# POWR0009.net
KiCad netlist of a schematic drawn in Altium Designer
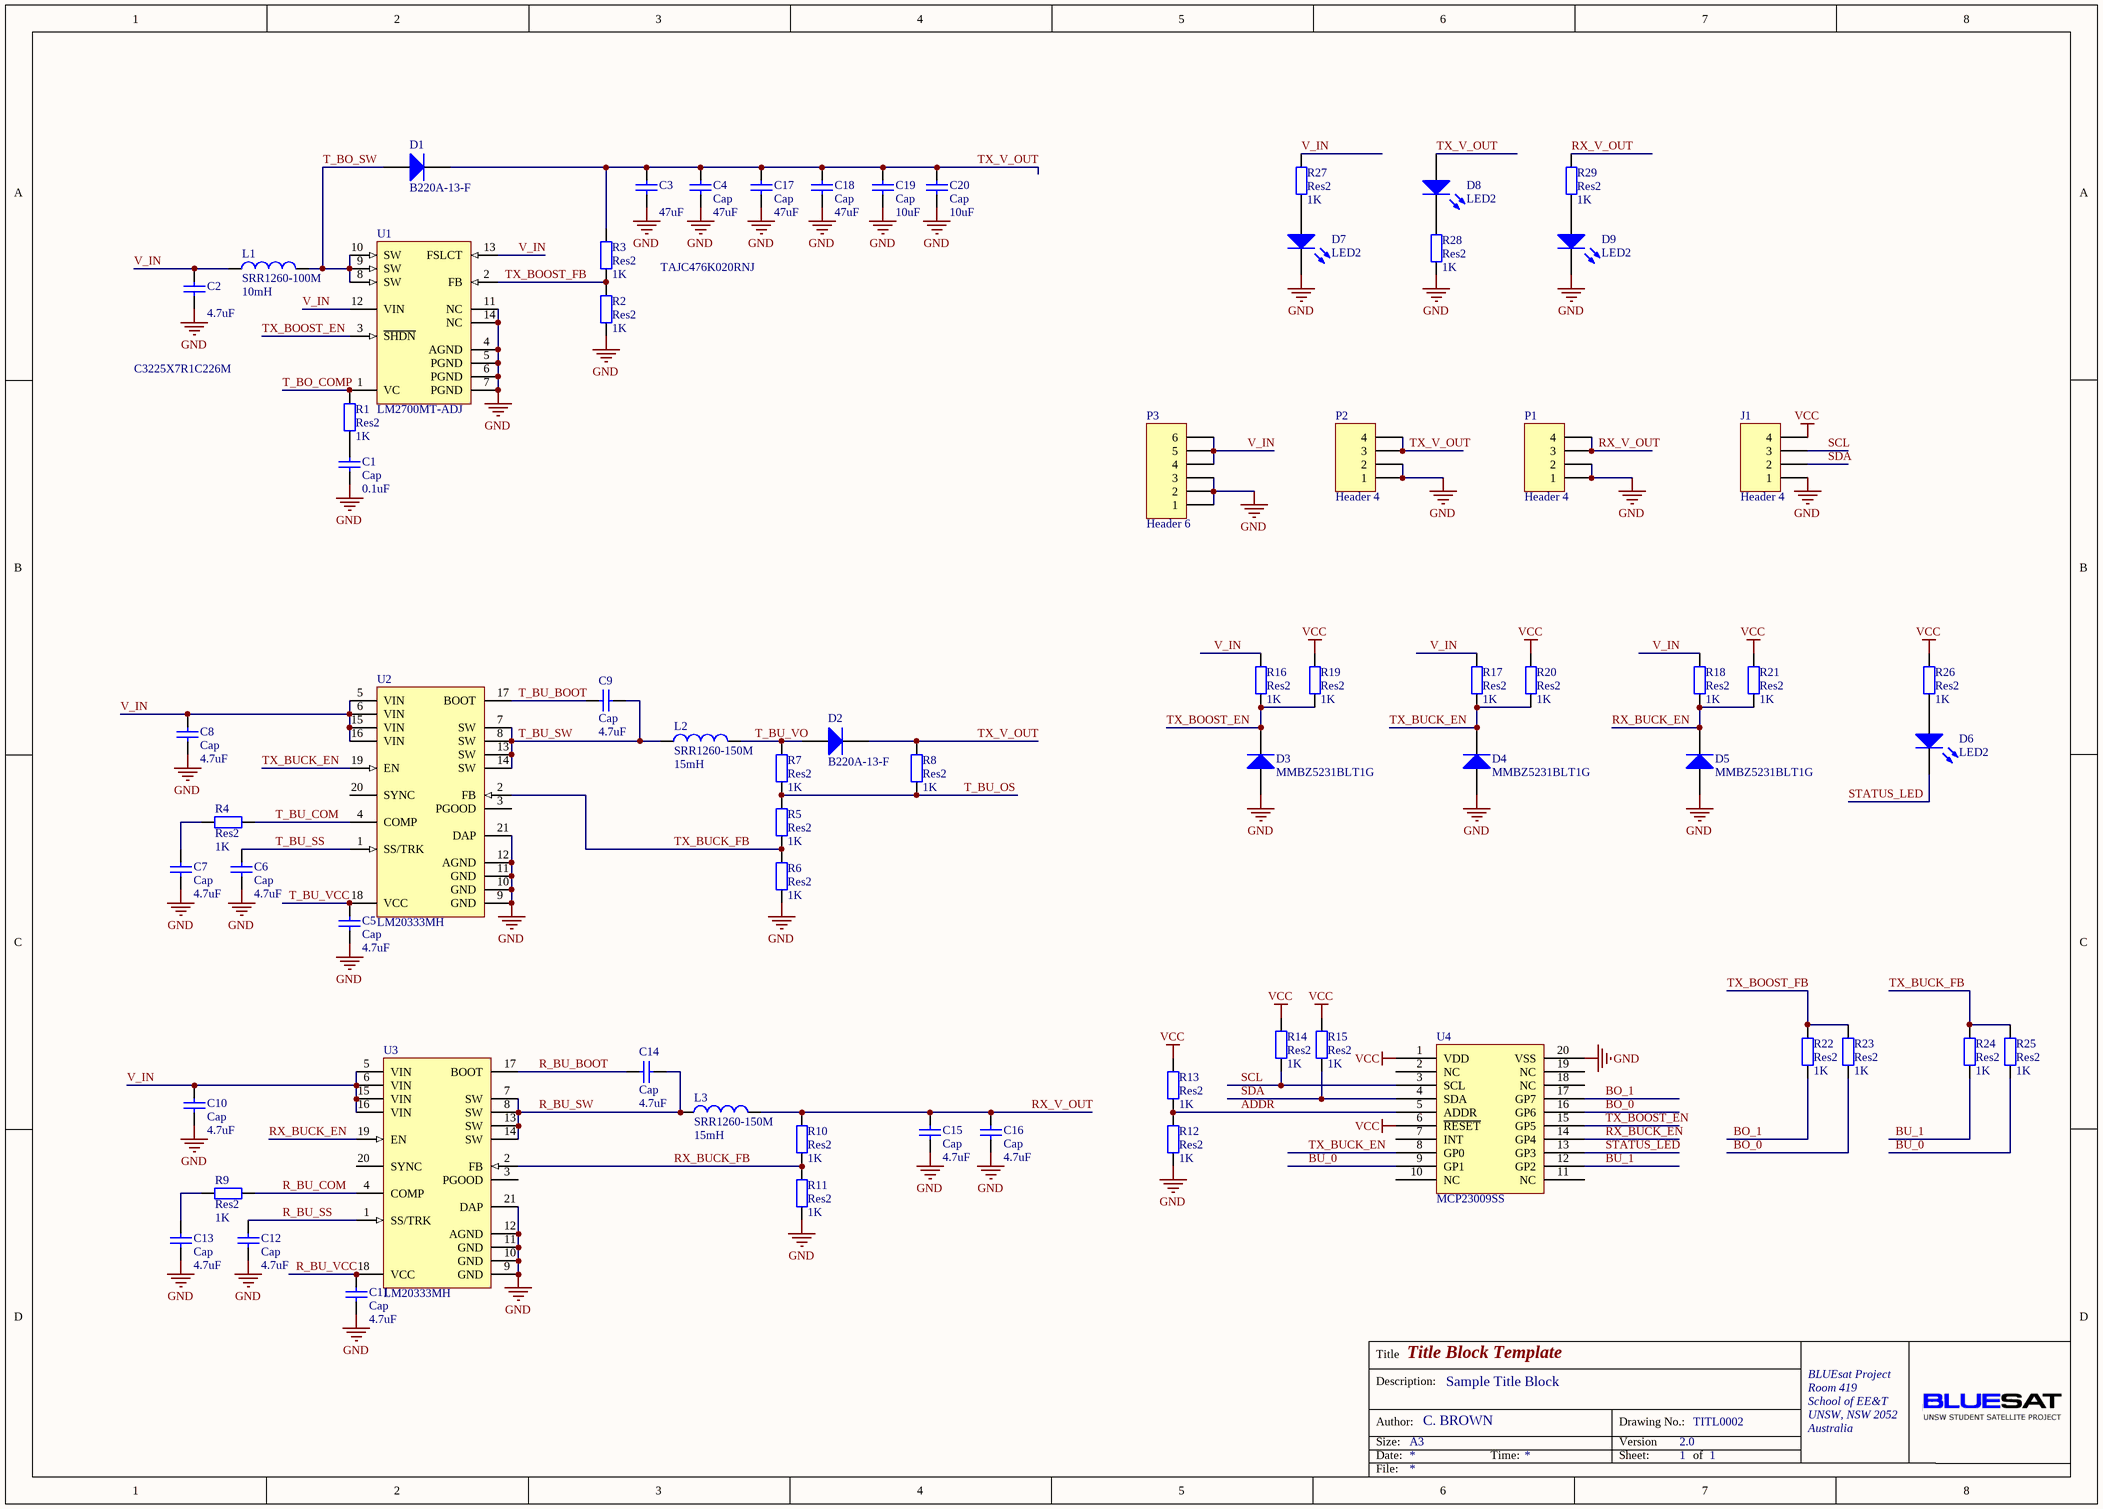
[diagram p0: POWR0009.SchDoc]

(export (version "E")
  (design (tool "Eeschema 10.0.6"))
  (components
    (comp (ref "C1")
      (value "Cap")
      (footprint "R0805M")
      (description "Capacitor")
      (fields (field (name "ALTIUM_VALUE") "0.1uF") (field (name "PUBLISHER") "Altium Limited"))
      (libsource (lib "Miscellaneous Devices") (part "Cap"))
    )
    (comp (ref "C2")
      (value "C3225X7R1C226M")
      (footprint "R1210M")
      (description "Capacitor")
      (fields (field (name "ALTIUM_VALUE") "4.7uF") (field (name "PUBLISHER") "Altium Limited"))
      (libsource (lib "Miscellaneous Devices") (part "Cap"))
    )
    (comp (ref "C3")
      (value "TAJC476K020RNJ")
      (footprint "TANTCASEC")
      (description "Capacitor")
      (fields (field (name "ALTIUM_VALUE") "47uF") (field (name "PUBLISHER") "Altium Limited"))
      (libsource (lib "Miscellaneous Devices") (part "Cap"))
    )
    (comp (ref "C4")
      (value "Cap")
      (footprint "TANTCASEC")
      (description "Capacitor")
      (fields (field (name "ALTIUM_VALUE") "47uF") (field (name "PUBLISHER") "Altium Limited"))
      (libsource (lib "Miscellaneous Devices") (part "Cap"))
    )
    (comp (ref "C5")
      (value "Cap")
      (footprint "R0805M")
      (description "Capacitor")
      (fields (field (name "ALTIUM_VALUE") "4.7uF") (field (name "PUBLISHER") "Altium Limited"))
      (libsource (lib "Miscellaneous Devices") (part "Cap"))
    )
    (comp (ref "C6")
      (value "Cap")
      (footprint "R0805M")
      (description "Capacitor")
      (fields (field (name "ALTIUM_VALUE") "4.7uF") (field (name "PUBLISHER") "Altium Limited"))
      (libsource (lib "Miscellaneous Devices") (part "Cap"))
    )
    (comp (ref "C7")
      (value "Cap")
      (footprint "R0805M")
      (description "Capacitor")
      (fields (field (name "ALTIUM_VALUE") "4.7uF") (field (name "PUBLISHER") "Altium Limited"))
      (libsource (lib "Miscellaneous Devices") (part "Cap"))
    )
    (comp (ref "C8")
      (value "Cap")
      (footprint "R1210M")
      (description "Capacitor")
      (fields (field (name "ALTIUM_VALUE") "4.7uF") (field (name "PUBLISHER") "Altium Limited"))
      (libsource (lib "Miscellaneous Devices") (part "Cap"))
    )
    (comp (ref "C9")
      (value "Cap")
      (footprint "R0805M")
      (description "Capacitor")
      (fields (field (name "ALTIUM_VALUE") "4.7uF") (field (name "PUBLISHER") "Altium Limited"))
      (libsource (lib "Miscellaneous Devices") (part "Cap"))
    )
    (comp (ref "C10")
      (value "Cap")
      (footprint "R1210M")
      (description "Capacitor")
      (fields (field (name "ALTIUM_VALUE") "4.7uF") (field (name "PUBLISHER") "Altium Limited"))
      (libsource (lib "Miscellaneous Devices") (part "Cap"))
    )
    (comp (ref "C11")
      (value "Cap")
      (footprint "R0805M")
      (description "Capacitor")
      (fields (field (name "ALTIUM_VALUE") "4.7uF") (field (name "PUBLISHER") "Altium Limited"))
      (libsource (lib "Miscellaneous Devices") (part "Cap"))
    )
    (comp (ref "C12")
      (value "Cap")
      (footprint "R0805M")
      (description "Capacitor")
      (fields (field (name "ALTIUM_VALUE") "4.7uF") (field (name "PUBLISHER") "Altium Limited"))
      (libsource (lib "Miscellaneous Devices") (part "Cap"))
    )
    (comp (ref "C13")
      (value "Cap")
      (footprint "R0805M")
      (description "Capacitor")
      (fields (field (name "ALTIUM_VALUE") "4.7uF") (field (name "PUBLISHER") "Altium Limited"))
      (libsource (lib "Miscellaneous Devices") (part "Cap"))
    )
    (comp (ref "C14")
      (value "Cap")
      (footprint "R0805M")
      (description "Capacitor")
      (fields (field (name "ALTIUM_VALUE") "4.7uF") (field (name "PUBLISHER") "Altium Limited"))
      (libsource (lib "Miscellaneous Devices") (part "Cap"))
    )
    (comp (ref "C15")
      (value "Cap")
      (footprint "R0805M")
      (description "Capacitor")
      (fields (field (name "ALTIUM_VALUE") "4.7uF") (field (name "PUBLISHER") "Altium Limited"))
      (libsource (lib "Miscellaneous Devices") (part "Cap"))
    )
    (comp (ref "C16")
      (value "Cap")
      (footprint "R0805M")
      (description "Capacitor")
      (fields (field (name "ALTIUM_VALUE") "4.7uF") (field (name "PUBLISHER") "Altium Limited"))
      (libsource (lib "Miscellaneous Devices") (part "Cap"))
    )
    (comp (ref "C17")
      (value "Cap")
      (footprint "TANTCASEC")
      (description "Capacitor")
      (fields (field (name "ALTIUM_VALUE") "47uF") (field (name "PUBLISHER") "Altium Limited"))
      (libsource (lib "Miscellaneous Devices") (part "Cap"))
    )
    (comp (ref "C18")
      (value "Cap")
      (footprint "TANTCASEC")
      (description "Capacitor")
      (fields (field (name "ALTIUM_VALUE") "47uF") (field (name "PUBLISHER") "Altium Limited"))
      (libsource (lib "Miscellaneous Devices") (part "Cap"))
    )
    (comp (ref "C19")
      (value "Cap")
      (footprint "R0805M")
      (description "Capacitor")
      (fields (field (name "ALTIUM_VALUE") "10uF") (field (name "PUBLISHER") "Altium Limited"))
      (libsource (lib "Miscellaneous Devices") (part "Cap"))
    )
    (comp (ref "C20")
      (value "Cap")
      (footprint "R0805M")
      (description "Capacitor")
      (fields (field (name "ALTIUM_VALUE") "10uF") (field (name "PUBLISHER") "Altium Limited"))
      (libsource (lib "Miscellaneous Devices") (part "Cap"))
    )
    (comp (ref "D1")
      (value "B220A-13-F")
      (footprint "DIODESMA")
      (description "High Conductance Fast Diode")
      (fields (field (name "PUBLISHER") "Altium Limited"))
      (libsource (lib "Miscellaneous Devices") (part "Diode 1N4148"))
    )
    (comp (ref "D2")
      (value "B220A-13-F")
      (footprint "DIODESMA")
      (description "High Conductance Fast Diode")
      (fields (field (name "PUBLISHER") "Altium Limited"))
      (libsource (lib "Miscellaneous Devices") (part "Diode 1N4148"))
    )
    (comp (ref "D3")
      (value "MMBZ5231BLT1G")
      (footprint "SOT95P240-3N")
      (description "Silicon Switching Diode for High-Speed Switching")
      (fields (field (name "PUBLISHER") "Altium Limited"))
      (libsource (lib "Miscellaneous Devices") (part "Diode BAS16"))
    )
    (comp (ref "D4")
      (value "MMBZ5231BLT1G")
      (footprint "SOT95P240-3N")
      (description "Silicon Switching Diode for High-Speed Switching")
      (fields (field (name "PUBLISHER") "Altium Limited"))
      (libsource (lib "Miscellaneous Devices") (part "Diode BAS16"))
    )
    (comp (ref "D5")
      (value "MMBZ5231BLT1G")
      (footprint "SOT95P240-3N")
      (description "Silicon Switching Diode for High-Speed Switching")
      (fields (field (name "PUBLISHER") "Altium Limited"))
      (libsource (lib "Miscellaneous Devices") (part "Diode BAS16"))
    )
    (comp (ref "D6")
      (value "LED2")
      (footprint "R0805M")
      (description "Typical RED, GREEN, YELLOW, AMBER GaAs LED")
      (fields (field (name "PUBLISHER") "Altium Limited"))
      (libsource (lib "Miscellaneous Devices") (part "LED2"))
    )
    (comp (ref "D7")
      (value "LED2")
      (footprint "R0805M")
      (description "Typical RED, GREEN, YELLOW, AMBER GaAs LED")
      (fields (field (name "PUBLISHER") "Altium Limited"))
      (libsource (lib "Miscellaneous Devices") (part "LED2"))
    )
    (comp (ref "D8")
      (value "LED2")
      (footprint "R0805M")
      (description "Typical RED, GREEN, YELLOW, AMBER GaAs LED")
      (fields (field (name "PUBLISHER") "Altium Limited"))
      (libsource (lib "Miscellaneous Devices") (part "LED2"))
    )
    (comp (ref "D9")
      (value "LED2")
      (footprint "R0805M")
      (description "Typical RED, GREEN, YELLOW, AMBER GaAs LED")
      (fields (field (name "PUBLISHER") "Altium Limited"))
      (libsource (lib "Miscellaneous Devices") (part "LED2"))
    )
    (comp (ref "J1")
      (value "Header 4")
      (footprint "HDR1X4")
      (description "Header, 4-Pin")
      (fields (field (name "PUBLISHER") "Altium Limited"))
      (libsource (lib "Miscellaneous Connectors") (part "Header 4"))
    )
    (comp (ref "L1")
      (value "SRR1260-100M")
      (footprint "SRR1260M")
      (description "Inductor")
      (fields (field (name "ALTIUM_VALUE") "10mH") (field (name "PUBLISHER") "Altium Limited"))
      (libsource (lib "Miscellaneous Devices") (part "Inductor"))
    )
    (comp (ref "L2")
      (value "SRR1260-150M")
      (footprint "SRR1260M")
      (description "Inductor")
      (fields (field (name "ALTIUM_VALUE") "15mH") (field (name "PUBLISHER") "Altium Limited"))
      (libsource (lib "Miscellaneous Devices") (part "Inductor"))
    )
    (comp (ref "L3")
      (value "SRR1260-150M")
      (footprint "SRR1260M")
      (description "Inductor")
      (fields (field (name "ALTIUM_VALUE") "15mH") (field (name "PUBLISHER") "Altium Limited"))
      (libsource (lib "Miscellaneous Devices") (part "Inductor"))
    )
    (comp (ref "P1")
      (value "Header 4")
      (footprint "HDR1X4")
      (description "Header, 4-Pin")
      (fields (field (name "PUBLISHER") "Altium Limited"))
      (libsource (lib "Miscellaneous Connectors") (part "Header 4"))
    )
    (comp (ref "P2")
      (value "Header 4")
      (footprint "HDR1X4")
      (description "Header, 4-Pin")
      (fields (field (name "PUBLISHER") "Altium Limited"))
      (libsource (lib "Miscellaneous Connectors") (part "Header 4"))
    )
    (comp (ref "P3")
      (value "Header 6")
      (footprint "HDR1X6")
      (description "Header, 6-Pin")
      (fields (field (name "PUBLISHER") "Altium Limited"))
      (libsource (lib "Miscellaneous Connectors") (part "Header 6"))
    )
    (comp (ref "R1")
      (value "Res2")
      (footprint "R0805M")
      (description "Resistor")
      (fields (field (name "ALTIUM_VALUE") "1K") (field (name "PUBLISHER") "Altium Limited"))
      (libsource (lib "Miscellaneous Devices") (part "Res2"))
    )
    (comp (ref "R2")
      (value "Res2")
      (footprint "R0805M")
      (description "Resistor")
      (fields (field (name "ALTIUM_VALUE") "1K") (field (name "PUBLISHER") "Altium Limited"))
      (libsource (lib "Miscellaneous Devices") (part "Res2"))
    )
    (comp (ref "R3")
      (value "Res2")
      (footprint "R0805M")
      (description "Resistor")
      (fields (field (name "ALTIUM_VALUE") "1K") (field (name "PUBLISHER") "Altium Limited"))
      (libsource (lib "Miscellaneous Devices") (part "Res2"))
    )
    (comp (ref "R4")
      (value "Res2")
      (footprint "R0805M")
      (description "Resistor")
      (fields (field (name "ALTIUM_VALUE") "1K") (field (name "PUBLISHER") "Altium Limited"))
      (libsource (lib "") (part "Res2_2"))
    )
    (comp (ref "R5")
      (value "Res2")
      (footprint "R0805M")
      (description "Resistor")
      (fields (field (name "ALTIUM_VALUE") "1K") (field (name "PUBLISHER") "Altium Limited"))
      (libsource (lib "") (part "Res2_1"))
    )
    (comp (ref "R6")
      (value "Res2")
      (footprint "R0805M")
      (description "Resistor")
      (fields (field (name "ALTIUM_VALUE") "1K") (field (name "PUBLISHER") "Altium Limited"))
      (libsource (lib "") (part "Res2_1"))
    )
    (comp (ref "R7")
      (value "Res2")
      (footprint "R0805M")
      (description "Resistor")
      (fields (field (name "ALTIUM_VALUE") "1K") (field (name "PUBLISHER") "Altium Limited"))
      (libsource (lib "") (part "Res2_1"))
    )
    (comp (ref "R8")
      (value "Res2")
      (footprint "R0805M")
      (description "Resistor")
      (fields (field (name "ALTIUM_VALUE") "1K") (field (name "PUBLISHER") "Altium Limited"))
      (libsource (lib "") (part "Res2_1"))
    )
    (comp (ref "R9")
      (value "Res2")
      (footprint "R0805M")
      (description "Resistor")
      (fields (field (name "ALTIUM_VALUE") "1K") (field (name "PUBLISHER") "Altium Limited"))
      (libsource (lib "") (part "Res2_2"))
    )
    (comp (ref "R10")
      (value "Res2")
      (footprint "R0805M")
      (description "Resistor")
      (fields (field (name "ALTIUM_VALUE") "1K") (field (name "PUBLISHER") "Altium Limited"))
      (libsource (lib "Miscellaneous Devices") (part "Res2"))
    )
    (comp (ref "R11")
      (value "Res2")
      (footprint "R0805M")
      (description "Resistor")
      (fields (field (name "ALTIUM_VALUE") "1K") (field (name "PUBLISHER") "Altium Limited"))
      (libsource (lib "Miscellaneous Devices") (part "Res2"))
    )
    (comp (ref "R12")
      (value "Res2")
      (footprint "R0805M")
      (description "Resistor")
      (fields (field (name "ALTIUM_VALUE") "1K") (field (name "PUBLISHER") "Altium Limited"))
      (libsource (lib "Miscellaneous Devices") (part "Res2"))
    )
    (comp (ref "R13")
      (value "Res2")
      (footprint "R0805M")
      (description "Resistor")
      (fields (field (name "ALTIUM_VALUE") "1K") (field (name "PUBLISHER") "Altium Limited"))
      (libsource (lib "Miscellaneous Devices") (part "Res2"))
    )
    (comp (ref "R14")
      (value "Res2")
      (footprint "R0805M")
      (description "Resistor")
      (fields (field (name "ALTIUM_VALUE") "1K") (field (name "PUBLISHER") "Altium Limited"))
      (libsource (lib "Miscellaneous Devices") (part "Res2"))
    )
    (comp (ref "R15")
      (value "Res2")
      (footprint "R0805M")
      (description "Resistor")
      (fields (field (name "ALTIUM_VALUE") "1K") (field (name "PUBLISHER") "Altium Limited"))
      (libsource (lib "Miscellaneous Devices") (part "Res2"))
    )
    (comp (ref "R16")
      (value "Res2")
      (footprint "R0805M")
      (description "Resistor")
      (fields (field (name "ALTIUM_VALUE") "1K") (field (name "PUBLISHER") "Altium Limited"))
      (libsource (lib "Miscellaneous Devices") (part "Res2"))
    )
    (comp (ref "R17")
      (value "Res2")
      (footprint "R0805M")
      (description "Resistor")
      (fields (field (name "ALTIUM_VALUE") "1K") (field (name "PUBLISHER") "Altium Limited"))
      (libsource (lib "Miscellaneous Devices") (part "Res2"))
    )
    (comp (ref "R18")
      (value "Res2")
      (footprint "R0805M")
      (description "Resistor")
      (fields (field (name "ALTIUM_VALUE") "1K") (field (name "PUBLISHER") "Altium Limited"))
      (libsource (lib "Miscellaneous Devices") (part "Res2"))
    )
    (comp (ref "R19")
      (value "Res2")
      (footprint "R0805M")
      (description "Resistor")
      (fields (field (name "ALTIUM_VALUE") "1K") (field (name "PUBLISHER") "Altium Limited"))
      (libsource (lib "Miscellaneous Devices") (part "Res2"))
    )
    (comp (ref "R20")
      (value "Res2")
      (footprint "R0805M")
      (description "Resistor")
      (fields (field (name "ALTIUM_VALUE") "1K") (field (name "PUBLISHER") "Altium Limited"))
      (libsource (lib "Miscellaneous Devices") (part "Res2"))
    )
    (comp (ref "R21")
      (value "Res2")
      (footprint "R0805M")
      (description "Resistor")
      (fields (field (name "ALTIUM_VALUE") "1K") (field (name "PUBLISHER") "Altium Limited"))
      (libsource (lib "Miscellaneous Devices") (part "Res2"))
    )
    (comp (ref "R22")
      (value "Res2")
      (footprint "R0805M")
      (description "Resistor")
      (fields (field (name "ALTIUM_VALUE") "1K") (field (name "PUBLISHER") "Altium Limited"))
      (libsource (lib "Miscellaneous Devices") (part "Res2"))
    )
    (comp (ref "R23")
      (value "Res2")
      (footprint "R0805M")
      (description "Resistor")
      (fields (field (name "ALTIUM_VALUE") "1K") (field (name "PUBLISHER") "Altium Limited"))
      (libsource (lib "Miscellaneous Devices") (part "Res2"))
    )
    (comp (ref "R24")
      (value "Res2")
      (footprint "R0805M")
      (description "Resistor")
      (fields (field (name "ALTIUM_VALUE") "1K") (field (name "PUBLISHER") "Altium Limited"))
      (libsource (lib "Miscellaneous Devices") (part "Res2"))
    )
    (comp (ref "R25")
      (value "Res2")
      (footprint "R0805M")
      (description "Resistor")
      (fields (field (name "ALTIUM_VALUE") "1K") (field (name "PUBLISHER") "Altium Limited"))
      (libsource (lib "Miscellaneous Devices") (part "Res2"))
    )
    (comp (ref "R26")
      (value "Res2")
      (footprint "R0805M")
      (description "Resistor")
      (fields (field (name "ALTIUM_VALUE") "1K") (field (name "PUBLISHER") "Altium Limited"))
      (libsource (lib "Miscellaneous Devices") (part "Res2"))
    )
    (comp (ref "R27")
      (value "Res2")
      (footprint "R0805M")
      (description "Resistor")
      (fields (field (name "ALTIUM_VALUE") "1K") (field (name "PUBLISHER") "Altium Limited"))
      (libsource (lib "Miscellaneous Devices") (part "Res2"))
    )
    (comp (ref "R28")
      (value "Res2")
      (footprint "R0805M")
      (description "Resistor")
      (fields (field (name "ALTIUM_VALUE") "1K") (field (name "PUBLISHER") "Altium Limited"))
      (libsource (lib "Miscellaneous Devices") (part "Res2"))
    )
    (comp (ref "R29")
      (value "Res2")
      (footprint "R0805M")
      (description "Resistor")
      (fields (field (name "ALTIUM_VALUE") "1K") (field (name "PUBLISHER") "Altium Limited"))
      (libsource (lib "Miscellaneous Devices") (part "Res2"))
    )
    (comp (ref "U1")
      (value "LM2700MT-ADJ")
      (footprint "MTC14_N")
      (description "600kHz/1.25MHz, 2.5A, Step-up PWM DC/DC Converter")
      (fields
        (field (name "MANUFACTURER") "National Semiconductor")
        (field (name "DIGIKEYPARTNUMBER") "LM2700MT-ADJ-ND")
        (field (name "PUBLISHER") "Altium Limited")
      )
      (libsource (lib "NSC Switcher") (part "LM2700MT-ADJ"))
    )
    (comp (ref "U2")
      (value "LM20333MH")
      (footprint "MXA20A_N")
      (description "36V, 3A PowerWise Synchronous Buck Regulator with Frequency Synchronization")
      (fields
        (field (name "MANUFACTURER") "National Semiconductor")
        (field (name "DIGIKEYPARTNUMBER") "LM20333MH-ND")
        (field (name "PUBLISHER") "Altium Limited")
      )
      (libsource (lib "NSC Switcher") (part "LM20333MH"))
    )
    (comp (ref "U3")
      (value "LM20333MH")
      (footprint "MXA20A_N")
      (description "36V, 3A PowerWise Synchronous Buck Regulator with Frequency Synchronization")
      (fields
        (field (name "MANUFACTURER") "National Semiconductor")
        (field (name "DIGIKEYPARTNUMBER") "LM20333MH-ND")
        (field (name "PUBLISHER") "Altium Limited")
      )
      (libsource (lib "NSC Switcher") (part "LM20333MH"))
    )
    (comp (ref "U4")
      (value "MCP23009SS")
      (footprint "SSOP-SS20_M")
      (libsource (lib "VarReg") (part "MCP23009SS"))
    )
  )
  (nets
    (net (code "1") (name "/ADDR") (class "Default")
      (node (ref "R12") (pin "2") (pinfunction "2_2") (pintype "passive"))
      (node (ref "R13") (pin "1") (pinfunction "1_1") (pintype "passive"))
      (node (ref "U4") (pin "5") (pinfunction "ADDR_5") (pintype "passive"))
    )
    (net (code "2") (name "/BO_0") (class "Default")
      (node (ref "R23") (pin "1") (pinfunction "1_1") (pintype "passive"))
      (node (ref "U4") (pin "16") (pinfunction "GP6_16") (pintype "passive"))
    )
    (net (code "3") (name "/BO_1") (class "Default")
      (node (ref "R22") (pin "1") (pinfunction "1_1") (pintype "passive"))
      (node (ref "U4") (pin "17") (pinfunction "GP7_17") (pintype "passive"))
    )
    (net (code "4") (name "/BU_0") (class "Default")
      (node (ref "R25") (pin "1") (pinfunction "1_1") (pintype "passive"))
      (node (ref "U4") (pin "9") (pinfunction "GP1_9") (pintype "passive"))
    )
    (net (code "5") (name "/BU_1") (class "Default")
      (node (ref "R24") (pin "1") (pinfunction "1_1") (pintype "passive"))
      (node (ref "U4") (pin "12") (pinfunction "GP2_12") (pintype "passive"))
    )
    (net (code "6") (name "/RX_BUCK_EN") (class "Default")
      (node (ref "D5") (pin "3") (pinfunction "K_3") (pintype "passive"))
      (node (ref "R18") (pin "1") (pinfunction "1_1") (pintype "passive"))
      (node (ref "R21") (pin "1") (pinfunction "1_1") (pintype "passive"))
      (node (ref "U3") (pin "19") (pinfunction "EN_19") (pintype "input"))
      (node (ref "U4") (pin "14") (pinfunction "GP4_14") (pintype "passive"))
    )
    (net (code "7") (name "/RX_BUCK_FB") (class "Default")
      (node (ref "R10") (pin "1") (pinfunction "1_1") (pintype "passive"))
      (node (ref "R11") (pin "2") (pinfunction "2_2") (pintype "passive"))
      (node (ref "U3") (pin "2") (pinfunction "FB_2") (pintype "input"))
    )
    (net (code "8") (name "/RX_V_OUT") (class "Default")
      (node (ref "C15") (pin "2") (pinfunction "2_2") (pintype "passive"))
      (node (ref "C16") (pin "2") (pinfunction "2_2") (pintype "passive"))
      (node (ref "L3") (pin "2") (pinfunction "2_2") (pintype "passive"))
      (node (ref "P1") (pin "3") (pinfunction "3_3") (pintype "passive"))
      (node (ref "P1") (pin "4") (pinfunction "4_4") (pintype "passive"))
      (node (ref "R10") (pin "2") (pinfunction "2_2") (pintype "passive"))
      (node (ref "R29") (pin "2") (pinfunction "2_2") (pintype "passive"))
    )
    (net (code "9") (name "/R_BU_BOOT") (class "Default")
      (node (ref "C14") (pin "1") (pinfunction "1_1") (pintype "passive"))
      (node (ref "U3") (pin "17") (pinfunction "BOOT_17") (pintype "passive"))
    )
    (net (code "10") (name "/R_BU_COM") (class "Default")
      (node (ref "R9") (pin "1") (pinfunction "1_1") (pintype "passive"))
      (node (ref "U3") (pin "4") (pinfunction "COMP_4") (pintype "passive"))
    )
    (net (code "11") (name "/R_BU_SS") (class "Default")
      (node (ref "C12") (pin "2") (pinfunction "2_2") (pintype "passive"))
      (node (ref "U3") (pin "1") (pinfunction "SS/TRK_1") (pintype "input"))
    )
    (net (code "12") (name "/R_BU_SW") (class "Default")
      (node (ref "C14") (pin "2") (pinfunction "2_2") (pintype "passive"))
      (node (ref "L3") (pin "1") (pinfunction "1_1") (pintype "passive"))
      (node (ref "U3") (pin "13") (pinfunction "SW_13") (pintype "power_in"))
      (node (ref "U3") (pin "14") (pinfunction "SW_14") (pintype "power_in"))
      (node (ref "U3") (pin "7") (pinfunction "SW_7") (pintype "power_in"))
      (node (ref "U3") (pin "8") (pinfunction "SW_8") (pintype "power_in"))
    )
    (net (code "13") (name "/R_BU_VCC") (class "Default")
      (node (ref "C11") (pin "2") (pinfunction "2_2") (pintype "passive"))
      (node (ref "U3") (pin "18") (pinfunction "VCC_18") (pintype "power_in"))
    )
    (net (code "14") (name "/SCL") (class "Default")
      (node (ref "J1") (pin "3") (pinfunction "3_3") (pintype "passive"))
      (node (ref "R14") (pin "1") (pinfunction "1_1") (pintype "passive"))
      (node (ref "U4") (pin "3") (pinfunction "SCL_3") (pintype "passive"))
    )
    (net (code "15") (name "/SDA") (class "Default")
      (node (ref "J1") (pin "2") (pinfunction "2_2") (pintype "passive"))
      (node (ref "R15") (pin "1") (pinfunction "1_1") (pintype "passive"))
      (node (ref "U4") (pin "4") (pinfunction "SDA_4") (pintype "passive"))
    )
    (net (code "16") (name "/STATUS_LED") (class "Default")
      (node (ref "D6") (pin "2") (pinfunction "K_2") (pintype "passive"))
      (node (ref "U4") (pin "13") (pinfunction "GP3_13") (pintype "passive"))
    )
    (net (code "17") (name "/TX_BOOST_EN") (class "Default")
      (node (ref "D3") (pin "3") (pinfunction "K_3") (pintype "passive"))
      (node (ref "R16") (pin "1") (pinfunction "1_1") (pintype "passive"))
      (node (ref "R19") (pin "1") (pinfunction "1_1") (pintype "passive"))
      (node (ref "U1") (pin "3") (pinfunction "~{SHDN}_3") (pintype "input"))
      (node (ref "U4") (pin "15") (pinfunction "GP5_15") (pintype "passive"))
    )
    (net (code "18") (name "/TX_BOOST_FB") (class "Default")
      (node (ref "R2") (pin "2") (pinfunction "2_2") (pintype "passive"))
      (node (ref "R22") (pin "2") (pinfunction "2_2") (pintype "passive"))
      (node (ref "R23") (pin "2") (pinfunction "2_2") (pintype "passive"))
      (node (ref "R3") (pin "1") (pinfunction "1_1") (pintype "passive"))
      (node (ref "U1") (pin "2") (pinfunction "FB_2") (pintype "input"))
    )
    (net (code "19") (name "/TX_BUCK_EN") (class "Default")
      (node (ref "D4") (pin "3") (pinfunction "K_3") (pintype "passive"))
      (node (ref "R17") (pin "1") (pinfunction "1_1") (pintype "passive"))
      (node (ref "R20") (pin "1") (pinfunction "1_1") (pintype "passive"))
      (node (ref "U2") (pin "19") (pinfunction "EN_19") (pintype "input"))
      (node (ref "U4") (pin "8") (pinfunction "GP0_8") (pintype "passive"))
    )
    (net (code "20") (name "/TX_BUCK_FB") (class "Default")
      (node (ref "R24") (pin "2") (pinfunction "2_2") (pintype "passive"))
      (node (ref "R25") (pin "2") (pinfunction "2_2") (pintype "passive"))
      (node (ref "R5") (pin "2") (pinfunction "2_2") (pintype "passive"))
      (node (ref "R6") (pin "1") (pinfunction "1_1") (pintype "passive"))
      (node (ref "U2") (pin "2") (pinfunction "FB_2") (pintype "input"))
    )
    (net (code "21") (name "/TX_V_OUT") (class "Default")
      (node (ref "C17") (pin "2") (pinfunction "2_2") (pintype "passive"))
      (node (ref "C18") (pin "2") (pinfunction "2_2") (pintype "passive"))
      (node (ref "C19") (pin "2") (pinfunction "2_2") (pintype "passive"))
      (node (ref "C20") (pin "2") (pinfunction "2_2") (pintype "passive"))
      (node (ref "C3") (pin "2") (pinfunction "2_2") (pintype "passive"))
      (node (ref "C4") (pin "2") (pinfunction "2_2") (pintype "passive"))
      (node (ref "D1") (pin "2") (pinfunction "K_2") (pintype "passive"))
      (node (ref "D2") (pin "2") (pinfunction "K_2") (pintype "passive"))
      (node (ref "D8") (pin "1") (pinfunction "A_1") (pintype "passive"))
      (node (ref "P2") (pin "3") (pinfunction "3_3") (pintype "passive"))
      (node (ref "P2") (pin "4") (pinfunction "4_4") (pintype "passive"))
      (node (ref "R3") (pin "2") (pinfunction "2_2") (pintype "passive"))
      (node (ref "R8") (pin "1") (pinfunction "1_1") (pintype "passive"))
    )
    (net (code "22") (name "/T_BO_COMP") (class "Default")
      (node (ref "R1") (pin "2") (pinfunction "2_2") (pintype "passive"))
      (node (ref "U1") (pin "1") (pinfunction "VC_1") (pintype "power_in"))
    )
    (net (code "23") (name "/T_BO_SW") (class "Default")
      (node (ref "D1") (pin "1") (pinfunction "A_1") (pintype "passive"))
      (node (ref "L1") (pin "2") (pinfunction "2_2") (pintype "passive"))
      (node (ref "U1") (pin "10") (pinfunction "SW_10") (pintype "input"))
      (node (ref "U1") (pin "8") (pinfunction "SW_8") (pintype "input"))
      (node (ref "U1") (pin "9") (pinfunction "SW_9") (pintype "input"))
    )
    (net (code "24") (name "/T_BU_BOOT") (class "Default")
      (node (ref "C9") (pin "2") (pinfunction "2_2") (pintype "passive"))
      (node (ref "U2") (pin "17") (pinfunction "BOOT_17") (pintype "passive"))
    )
    (net (code "25") (name "/T_BU_COM") (class "Default")
      (node (ref "R4") (pin "1") (pinfunction "1_1") (pintype "passive"))
      (node (ref "U2") (pin "4") (pinfunction "COMP_4") (pintype "passive"))
    )
    (net (code "26") (name "/T_BU_OS") (class "Default")
      (node (ref "R5") (pin "1") (pinfunction "1_1") (pintype "passive"))
      (node (ref "R7") (pin "2") (pinfunction "2_2") (pintype "passive"))
      (node (ref "R8") (pin "2") (pinfunction "2_2") (pintype "passive"))
    )
    (net (code "27") (name "/T_BU_SS") (class "Default")
      (node (ref "C6") (pin "2") (pinfunction "2_2") (pintype "passive"))
      (node (ref "U2") (pin "1") (pinfunction "SS/TRK_1") (pintype "input"))
    )
    (net (code "28") (name "/T_BU_SW") (class "Default")
      (node (ref "C9") (pin "1") (pinfunction "1_1") (pintype "passive"))
      (node (ref "L2") (pin "1") (pinfunction "1_1") (pintype "passive"))
      (node (ref "U2") (pin "13") (pinfunction "SW_13") (pintype "power_in"))
      (node (ref "U2") (pin "14") (pinfunction "SW_14") (pintype "power_in"))
      (node (ref "U2") (pin "7") (pinfunction "SW_7") (pintype "power_in"))
      (node (ref "U2") (pin "8") (pinfunction "SW_8") (pintype "power_in"))
    )
    (net (code "29") (name "/T_BU_VCC") (class "Default")
      (node (ref "C5") (pin "2") (pinfunction "2_2") (pintype "passive"))
      (node (ref "U2") (pin "18") (pinfunction "VCC_18") (pintype "power_in"))
    )
    (net (code "30") (name "/T_BU_VO") (class "Default")
      (node (ref "D2") (pin "1") (pinfunction "A_1") (pintype "passive"))
      (node (ref "L2") (pin "2") (pinfunction "2_2") (pintype "passive"))
      (node (ref "R7") (pin "1") (pinfunction "1_1") (pintype "passive"))
    )
    (net (code "31") (name "/V_IN") (class "Default")
      (node (ref "C10") (pin "2") (pinfunction "2_2") (pintype "passive"))
      (node (ref "C2") (pin "2") (pinfunction "2_2") (pintype "passive"))
      (node (ref "C8") (pin "2") (pinfunction "2_2") (pintype "passive"))
      (node (ref "L1") (pin "1") (pinfunction "1_1") (pintype "passive"))
      (node (ref "P3") (pin "4") (pinfunction "4_4") (pintype "passive"))
      (node (ref "P3") (pin "5") (pinfunction "5_5") (pintype "passive"))
      (node (ref "P3") (pin "6") (pinfunction "6_6") (pintype "passive"))
      (node (ref "R16") (pin "2") (pinfunction "2_2") (pintype "passive"))
      (node (ref "R17") (pin "2") (pinfunction "2_2") (pintype "passive"))
      (node (ref "R18") (pin "2") (pinfunction "2_2") (pintype "passive"))
      (node (ref "R27") (pin "2") (pinfunction "2_2") (pintype "passive"))
      (node (ref "U1") (pin "12") (pinfunction "VIN_12") (pintype "power_in"))
      (node (ref "U1") (pin "13") (pinfunction "FSLCT_13") (pintype "input"))
      (node (ref "U2") (pin "15") (pinfunction "VIN_15") (pintype "power_in"))
      (node (ref "U2") (pin "16") (pinfunction "VIN_16") (pintype "power_in"))
      (node (ref "U2") (pin "5") (pinfunction "VIN_5") (pintype "power_in"))
      (node (ref "U2") (pin "6") (pinfunction "VIN_6") (pintype "power_in"))
      (node (ref "U3") (pin "15") (pinfunction "VIN_15") (pintype "power_in"))
      (node (ref "U3") (pin "16") (pinfunction "VIN_16") (pintype "power_in"))
      (node (ref "U3") (pin "5") (pinfunction "VIN_5") (pintype "power_in"))
      (node (ref "U3") (pin "6") (pinfunction "VIN_6") (pintype "power_in"))
    )
    (net (code "32") (name "GND") (class "Default")
      (node (ref "C1") (pin "1") (pinfunction "1_1") (pintype "passive"))
      (node (ref "C10") (pin "1") (pinfunction "1_1") (pintype "passive"))
      (node (ref "C11") (pin "1") (pinfunction "1_1") (pintype "passive"))
      (node (ref "C12") (pin "1") (pinfunction "1_1") (pintype "passive"))
      (node (ref "C13") (pin "1") (pinfunction "1_1") (pintype "passive"))
      (node (ref "C15") (pin "1") (pinfunction "1_1") (pintype "passive"))
      (node (ref "C16") (pin "1") (pinfunction "1_1") (pintype "passive"))
      (node (ref "C17") (pin "1") (pinfunction "1_1") (pintype "passive"))
      (node (ref "C18") (pin "1") (pinfunction "1_1") (pintype "passive"))
      (node (ref "C19") (pin "1") (pinfunction "1_1") (pintype "passive"))
      (node (ref "C2") (pin "1") (pinfunction "1_1") (pintype "passive"))
      (node (ref "C20") (pin "1") (pinfunction "1_1") (pintype "passive"))
      (node (ref "C3") (pin "1") (pinfunction "1_1") (pintype "passive"))
      (node (ref "C4") (pin "1") (pinfunction "1_1") (pintype "passive"))
      (node (ref "C5") (pin "1") (pinfunction "1_1") (pintype "passive"))
      (node (ref "C6") (pin "1") (pinfunction "1_1") (pintype "passive"))
      (node (ref "C7") (pin "1") (pinfunction "1_1") (pintype "passive"))
      (node (ref "C8") (pin "1") (pinfunction "1_1") (pintype "passive"))
      (node (ref "D3") (pin "1") (pinfunction "A_1") (pintype "passive"))
      (node (ref "D4") (pin "1") (pinfunction "A_1") (pintype "passive"))
      (node (ref "D5") (pin "1") (pinfunction "A_1") (pintype "passive"))
      (node (ref "D7") (pin "2") (pinfunction "K_2") (pintype "passive"))
      (node (ref "D9") (pin "2") (pinfunction "K_2") (pintype "passive"))
      (node (ref "J1") (pin "1") (pinfunction "1_1") (pintype "passive"))
      (node (ref "P1") (pin "1") (pinfunction "1_1") (pintype "passive"))
      (node (ref "P1") (pin "2") (pinfunction "2_2") (pintype "passive"))
      (node (ref "P2") (pin "1") (pinfunction "1_1") (pintype "passive"))
      (node (ref "P2") (pin "2") (pinfunction "2_2") (pintype "passive"))
      (node (ref "P3") (pin "1") (pinfunction "1_1") (pintype "passive"))
      (node (ref "P3") (pin "2") (pinfunction "2_2") (pintype "passive"))
      (node (ref "P3") (pin "3") (pinfunction "3_3") (pintype "passive"))
      (node (ref "R11") (pin "1") (pinfunction "1_1") (pintype "passive"))
      (node (ref "R12") (pin "1") (pinfunction "1_1") (pintype "passive"))
      (node (ref "R2") (pin "1") (pinfunction "1_1") (pintype "passive"))
      (node (ref "R28") (pin "1") (pinfunction "1_1") (pintype "passive"))
      (node (ref "R6") (pin "2") (pinfunction "2_2") (pintype "passive"))
      (node (ref "U1") (pin "11") (pinfunction "NC_11") (pintype "passive"))
      (node (ref "U1") (pin "14") (pinfunction "NC_14") (pintype "passive"))
      (node (ref "U1") (pin "4") (pinfunction "AGND_4") (pintype "power_in"))
      (node (ref "U1") (pin "5") (pinfunction "PGND_5") (pintype "power_in"))
      (node (ref "U1") (pin "6") (pinfunction "PGND_6") (pintype "power_in"))
      (node (ref "U1") (pin "7") (pinfunction "PGND_7") (pintype "power_in"))
      (node (ref "U2") (pin "10") (pinfunction "GND_10") (pintype "power_in"))
      (node (ref "U2") (pin "11") (pinfunction "GND_11") (pintype "power_in"))
      (node (ref "U2") (pin "12") (pinfunction "AGND_12") (pintype "power_in"))
      (node (ref "U2") (pin "21") (pinfunction "DAP_21") (pintype "power_in"))
      (node (ref "U2") (pin "9") (pinfunction "GND_9") (pintype "power_in"))
      (node (ref "U3") (pin "10") (pinfunction "GND_10") (pintype "power_in"))
      (node (ref "U3") (pin "11") (pinfunction "GND_11") (pintype "power_in"))
      (node (ref "U3") (pin "12") (pinfunction "AGND_12") (pintype "power_in"))
      (node (ref "U3") (pin "21") (pinfunction "DAP_21") (pintype "power_in"))
      (node (ref "U3") (pin "9") (pinfunction "GND_9") (pintype "power_in"))
      (node (ref "U4") (pin "20") (pinfunction "VSS_20") (pintype "passive"))
    )
    (net (code "33") (name "Net-(C1-Pad2)") (class "Default")
      (node (ref "C1") (pin "2") (pinfunction "2_2") (pintype "passive"))
      (node (ref "R1") (pin "1") (pinfunction "1_1") (pintype "passive"))
    )
    (net (code "34") (name "Net-(C7-Pad2)") (class "Default")
      (node (ref "C7") (pin "2") (pinfunction "2_2") (pintype "passive"))
      (node (ref "R4") (pin "2") (pinfunction "2_2") (pintype "passive"))
    )
    (net (code "35") (name "Net-(C13-Pad2)") (class "Default")
      (node (ref "C13") (pin "2") (pinfunction "2_2") (pintype "passive"))
      (node (ref "R9") (pin "2") (pinfunction "2_2") (pintype "passive"))
    )
    (net (code "36") (name "Net-(D6-A)") (class "Default")
      (node (ref "D6") (pin "1") (pinfunction "A_1") (pintype "passive"))
      (node (ref "R26") (pin "1") (pinfunction "1_1") (pintype "passive"))
    )
    (net (code "37") (name "Net-(D7-A)") (class "Default")
      (node (ref "D7") (pin "1") (pinfunction "A_1") (pintype "passive"))
      (node (ref "R27") (pin "1") (pinfunction "1_1") (pintype "passive"))
    )
    (net (code "38") (name "Net-(D8-K)") (class "Default")
      (node (ref "D8") (pin "2") (pinfunction "K_2") (pintype "passive"))
      (node (ref "R28") (pin "2") (pinfunction "2_2") (pintype "passive"))
    )
    (net (code "39") (name "Net-(D9-A)") (class "Default")
      (node (ref "D9") (pin "1") (pinfunction "A_1") (pintype "passive"))
      (node (ref "R29") (pin "1") (pinfunction "1_1") (pintype "passive"))
    )
    (net (code "40") (name "VCC") (class "Default")
      (node (ref "J1") (pin "4") (pinfunction "4_4") (pintype "passive"))
      (node (ref "R13") (pin "2") (pinfunction "2_2") (pintype "passive"))
      (node (ref "R14") (pin "2") (pinfunction "2_2") (pintype "passive"))
      (node (ref "R15") (pin "2") (pinfunction "2_2") (pintype "passive"))
      (node (ref "R19") (pin "2") (pinfunction "2_2") (pintype "passive"))
      (node (ref "R20") (pin "2") (pinfunction "2_2") (pintype "passive"))
      (node (ref "R21") (pin "2") (pinfunction "2_2") (pintype "passive"))
      (node (ref "R26") (pin "2") (pinfunction "2_2") (pintype "passive"))
      (node (ref "U4") (pin "1") (pinfunction "VDD_1") (pintype "passive"))
      (node (ref "U4") (pin "6") (pinfunction "~{RESET}_6") (pintype "passive"))
    )
    (net (code "41") (name "unconnected-(U2-PGOOD-Pad3)") (class "Default")
      (node (ref "U2") (pin "3") (pinfunction "PGOOD_3") (pintype "open_collector"))
    )
    (net (code "42") (name "unconnected-(U2-SYNC-Pad20)") (class "Default")
      (node (ref "U2") (pin "20") (pinfunction "SYNC_20") (pintype "passive"))
    )
    (net (code "43") (name "unconnected-(U3-PGOOD-Pad3)") (class "Default")
      (node (ref "U3") (pin "3") (pinfunction "PGOOD_3") (pintype "open_collector"))
    )
    (net (code "44") (name "unconnected-(U3-SYNC-Pad20)") (class "Default")
      (node (ref "U3") (pin "20") (pinfunction "SYNC_20") (pintype "passive"))
    )
    (net (code "45") (name "unconnected-(U4-INT-Pad7)") (class "Default")
      (node (ref "U4") (pin "7") (pinfunction "INT_7") (pintype "passive"))
    )
    (net (code "46") (name "unconnected-(U4-NC-Pad2)") (class "Default")
      (node (ref "U4") (pin "2") (pinfunction "NC_2") (pintype "passive"))
    )
    (net (code "47") (name "unconnected-(U4-NC-Pad10)") (class "Default")
      (node (ref "U4") (pin "10") (pinfunction "NC_10") (pintype "passive"))
    )
    (net (code "48") (name "unconnected-(U4-NC-Pad11)") (class "Default")
      (node (ref "U4") (pin "11") (pinfunction "NC_11") (pintype "passive"))
    )
    (net (code "49") (name "unconnected-(U4-NC-Pad18)") (class "Default")
      (node (ref "U4") (pin "18") (pinfunction "NC_18") (pintype "passive"))
    )
    (net (code "50") (name "unconnected-(U4-NC-Pad19)") (class "Default")
      (node (ref "U4") (pin "19") (pinfunction "NC_19") (pintype "passive"))
    )
  )
)
